# LM7171SMD.net
KiCad netlist of a schematic drawn in Altium Designer
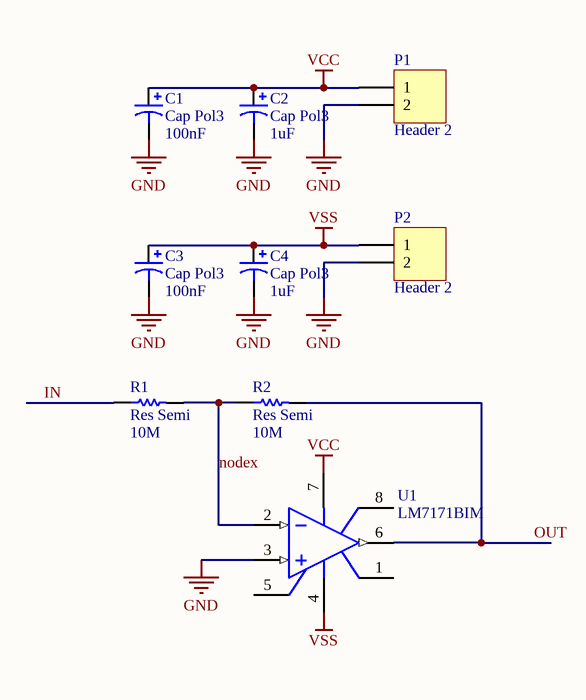
[diagram p0: LM7171SMD.SchDoc]

(export (version "E")
  (design (tool "Eeschema 10.0.6"))
  (components
    (comp (ref "C1")
      (value "Cap Pol3")
      (footprint "C0805")
      (description "Polarized Capacitor (Surface Mount)")
      (fields (field (name "ALTIUM_VALUE") "100nF") (field (name "PUBLISHER") "Altium Limited"))
      (libsource (lib "Miscellaneous Devices") (part "Cap Pol3"))
    )
    (comp (ref "C2")
      (value "Cap Pol3")
      (footprint "C0805")
      (description "Polarized Capacitor (Surface Mount)")
      (fields (field (name "ALTIUM_VALUE") "1uF") (field (name "PUBLISHER") "Altium Limited"))
      (libsource (lib "Miscellaneous Devices") (part "Cap Pol3"))
    )
    (comp (ref "C3")
      (value "Cap Pol3")
      (footprint "C0805")
      (description "Polarized Capacitor (Surface Mount)")
      (fields (field (name "ALTIUM_VALUE") "100nF") (field (name "PUBLISHER") "Altium Limited"))
      (libsource (lib "Miscellaneous Devices") (part "Cap Pol3"))
    )
    (comp (ref "C4")
      (value "Cap Pol3")
      (footprint "C0805")
      (description "Polarized Capacitor (Surface Mount)")
      (fields (field (name "ALTIUM_VALUE") "1uF") (field (name "PUBLISHER") "Altium Limited"))
      (libsource (lib "Miscellaneous Devices") (part "Cap Pol3"))
    )
    (comp (ref "P1")
      (value "Header 2")
      (footprint "HDR1X2")
      (description "Header, 2-Pin")
      (fields (field (name "PUBLISHER") "Altium Limited"))
      (libsource (lib "Miscellaneous Connectors") (part "Header 2"))
    )
    (comp (ref "P2")
      (value "Header 2")
      (footprint "HDR1X2")
      (description "Header, 2-Pin")
      (fields (field (name "PUBLISHER") "Altium Limited"))
      (libsource (lib "Miscellaneous Connectors") (part "Header 2"))
    )
    (comp (ref "R1")
      (value "Res Semi")
      (footprint "2012[0805]")
      (description "Semiconductor Resistor")
      (fields (field (name "ALTIUM_VALUE") "10M") (field (name "PUBLISHER") "Altium Limited"))
      (libsource (lib "Miscellaneous Devices") (part "Res Semi"))
    )
    (comp (ref "R2")
      (value "Res Semi")
      (footprint "2012[0805]")
      (description "Semiconductor Resistor")
      (fields (field (name "ALTIUM_VALUE") "10M") (field (name "PUBLISHER") "Altium Limited"))
      (libsource (lib "Miscellaneous Devices") (part "Res Semi"))
    )
    (comp (ref "U1")
      (value "LM7171BIM")
      (footprint "D008_M")
      (description "Operational Amplifier")
      (fields (field (name "PUBLISHER") "Altium Limited"))
      (libsource (lib "TI Operational Amplifier") (part "LF351D"))
    )
  )
  (nets
    (net (code "1") (name "/IN") (class "Default")
      (node (ref "R1") (pin "1") (pinfunction "1_1") (pintype "passive"))
    )
    (net (code "2") (name "/OUT") (class "Default")
      (node (ref "R2") (pin "2") (pinfunction "2_2") (pintype "passive"))
      (node (ref "U1") (pin "6") (pinfunction "OUT_6") (pintype "output"))
    )
    (net (code "3") (name "/nodex") (class "Default")
      (node (ref "R1") (pin "2") (pinfunction "2_2") (pintype "passive"))
      (node (ref "R2") (pin "1") (pinfunction "1_1") (pintype "passive"))
      (node (ref "U1") (pin "2") (pinfunction "IN-_2") (pintype "input"))
    )
    (net (code "4") (name "GND") (class "Default")
      (node (ref "C1") (pin "2") (pinfunction "2_2") (pintype "passive"))
      (node (ref "C2") (pin "2") (pinfunction "2_2") (pintype "passive"))
      (node (ref "C3") (pin "2") (pinfunction "2_2") (pintype "passive"))
      (node (ref "C4") (pin "2") (pinfunction "2_2") (pintype "passive"))
      (node (ref "P1") (pin "2") (pinfunction "2_2") (pintype "passive"))
      (node (ref "P2") (pin "2") (pinfunction "2_2") (pintype "passive"))
      (node (ref "U1") (pin "3") (pinfunction "IN+_3") (pintype "input"))
    )
    (net (code "5") (name "VCC") (class "Default")
      (node (ref "C1") (pin "1") (pinfunction "1_1") (pintype "passive"))
      (node (ref "C2") (pin "1") (pinfunction "1_1") (pintype "passive"))
      (node (ref "P1") (pin "1") (pinfunction "1_1") (pintype "passive"))
      (node (ref "U1") (pin "7") (pinfunction "V+_7") (pintype "power_in"))
    )
    (net (code "6") (name "VSS") (class "Default")
      (node (ref "C3") (pin "1") (pinfunction "1_1") (pintype "passive"))
      (node (ref "C4") (pin "1") (pinfunction "1_1") (pintype "passive"))
      (node (ref "P2") (pin "1") (pinfunction "1_1") (pintype "passive"))
      (node (ref "U1") (pin "4") (pinfunction "V-_4") (pintype "power_in"))
    )
    (net (code "7") (name "unconnected-(U1-NC-Pad8)") (class "Default")
      (node (ref "U1") (pin "8") (pinfunction "NC_8") (pintype "passive"))
    )
    (net (code "8") (name "unconnected-(U1-OS_TRIM-Pad1)") (class "Default")
      (node (ref "U1") (pin "1") (pinfunction "OS_TRIM_1") (pintype "passive"))
    )
    (net (code "9") (name "unconnected-(U1-OS_TRIM-Pad5)") (class "Default")
      (node (ref "U1") (pin "5") (pinfunction "OS_TRIM_5") (pintype "passive"))
    )
  )
)
